# STM32.net
KiCad netlist of a schematic drawn in Altium Designer
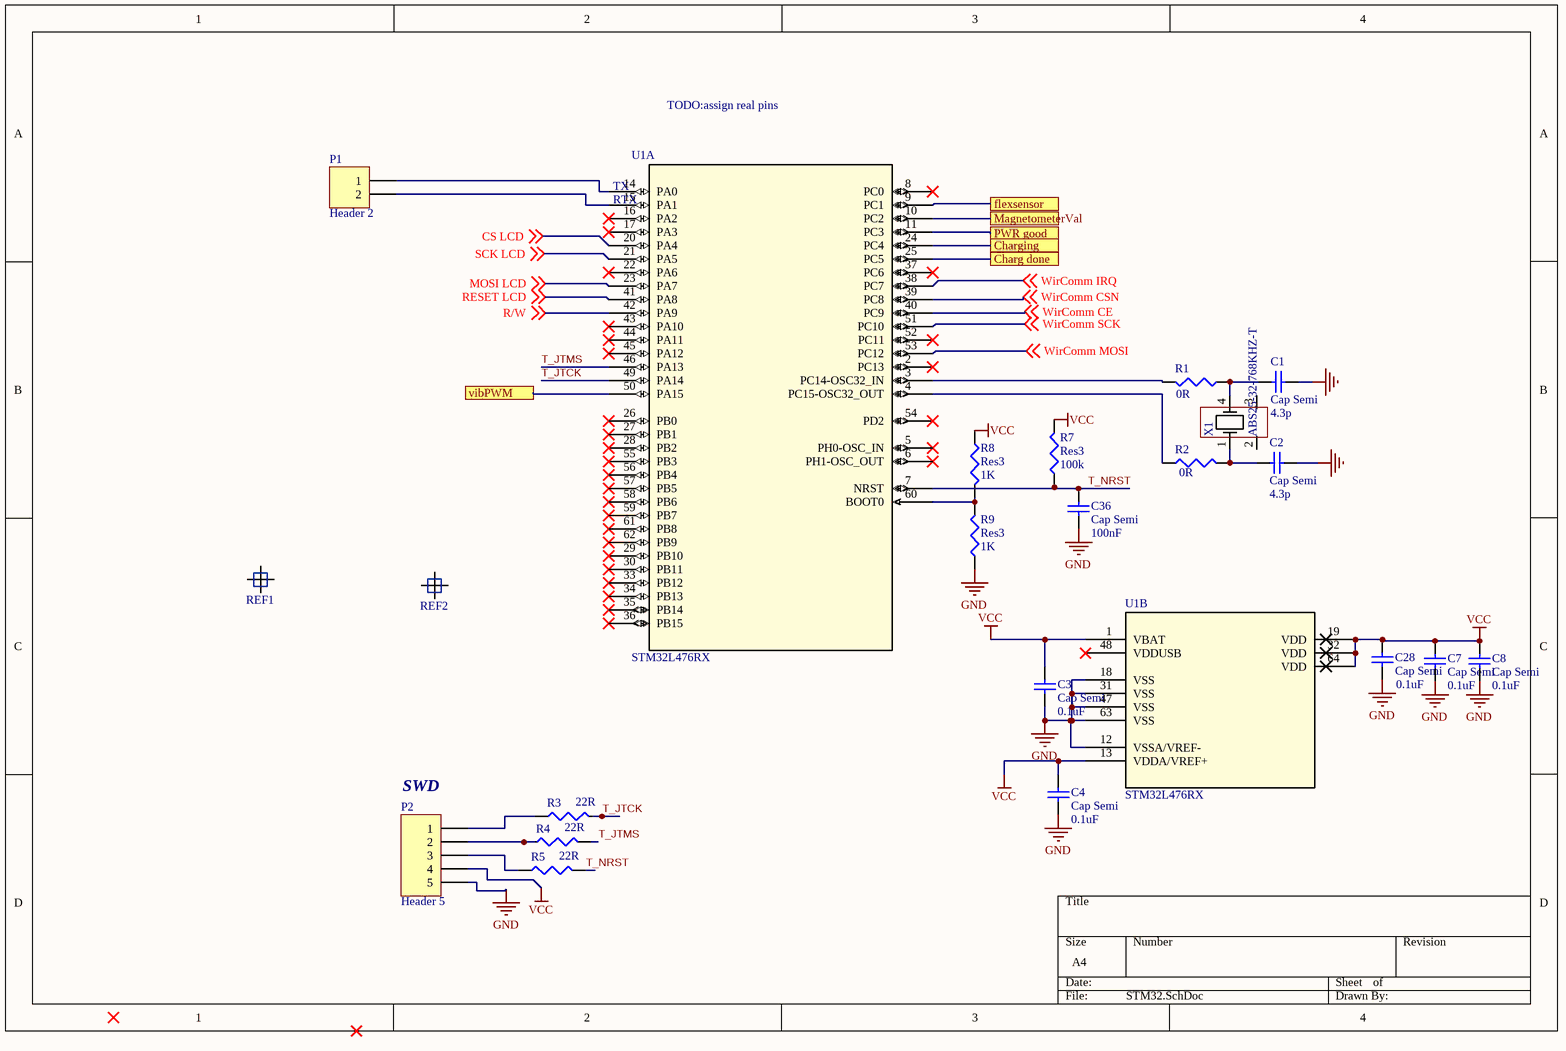
[diagram p0: STM32.SchDoc]

(export (version "E")
  (design (tool "Eeschema 10.0.6"))
  (components
    (comp (ref "C1")
      (value "Cap Semi")
      (footprint "1608[0603]")
      (description "Capacitor (Semiconductor SIM Model)")
      (fields (field (name "ALTIUM_VALUE") "4.3p") (field (name "PUBLISHER") "Altium Limited"))
      (libsource (lib "Miscellaneous Devices") (part "Cap Semi"))
    )
    (comp (ref "C2")
      (value "Cap Semi")
      (footprint "1608[0603]")
      (description "Capacitor (Semiconductor SIM Model)")
      (fields (field (name "ALTIUM_VALUE") "4.3p") (field (name "PUBLISHER") "Altium Limited"))
      (libsource (lib "Miscellaneous Devices") (part "Cap Semi"))
    )
    (comp (ref "C3")
      (value "Cap Semi")
      (footprint "1608[0603]")
      (description "Capacitor (Semiconductor SIM Model)")
      (fields (field (name "ALTIUM_VALUE") "0.1uF") (field (name "PUBLISHER") "Altium Limited"))
      (libsource (lib "Miscellaneous Devices") (part "Cap Semi"))
    )
    (comp (ref "C4")
      (value "Cap Semi")
      (footprint "1608[0603]")
      (description "Capacitor (Semiconductor SIM Model)")
      (fields (field (name "ALTIUM_VALUE") "0.1uF") (field (name "PUBLISHER") "Altium Limited"))
      (libsource (lib "Miscellaneous Devices") (part "Cap Semi"))
    )
    (comp (ref "C7")
      (value "Cap Semi")
      (footprint "1608[0603]")
      (description "Capacitor (Semiconductor SIM Model)")
      (fields (field (name "ALTIUM_VALUE") "0.1uF") (field (name "PUBLISHER") "Altium Limited"))
      (libsource (lib "Miscellaneous Devices") (part "Cap Semi"))
    )
    (comp (ref "C8")
      (value "Cap Semi")
      (footprint "1608[0603]")
      (description "Capacitor (Semiconductor SIM Model)")
      (fields (field (name "ALTIUM_VALUE") "0.1uF") (field (name "PUBLISHER") "Altium Limited"))
      (libsource (lib "Miscellaneous Devices") (part "Cap Semi"))
    )
    (comp (ref "C28")
      (value "Cap Semi")
      (footprint "1608[0603]")
      (description "Capacitor (Semiconductor SIM Model)")
      (fields (field (name "ALTIUM_VALUE") "0.1uF") (field (name "PUBLISHER") "Altium Limited"))
      (libsource (lib "Miscellaneous Devices") (part "Cap Semi"))
    )
    (comp (ref "C36")
      (value "Cap Semi")
      (footprint "1608[0603]")
      (description "Capacitor (Semiconductor SIM Model)")
      (fields (field (name "ALTIUM_VALUE") "100nF") (field (name "PUBLISHER") "Altium Limited"))
      (libsource (lib "Miscellaneous Devices") (part "Cap Semi"))
    )
    (comp (ref "P1")
      (value "Header 2")
      (footprint "HDR1X2")
      (description "Header, 2-Pin")
      (fields (field (name "PUBLISHER") "Altium Limited"))
      (libsource (lib "Miscellaneous Connectors") (part "Header 2"))
    )
    (comp (ref "P2")
      (value "Header 5")
      (footprint "HDR1X5")
      (description "Header, 5-Pin")
      (fields (field (name "PUBLISHER") "Altium Limited"))
      (libsource (lib "Miscellaneous Connectors") (part "Header 5"))
    )
    (comp (ref "R1")
      (value "0R")
      (footprint "J1-0603")
      (description "Resistor")
      (fields (field (name "Comment") "Res3") (field (name "PUBLISHER") "Altium Limited"))
      (libsource (lib "Miscellaneous Devices") (part "Res3"))
    )
    (comp (ref "R2")
      (value "0R")
      (footprint "J1-0603")
      (description "Resistor")
      (fields (field (name "Comment") "Res3") (field (name "PUBLISHER") "Altium Limited"))
      (libsource (lib "Miscellaneous Devices") (part "Res3"))
    )
    (comp (ref "R3")
      (value "22R")
      (footprint "J1-0603")
      (description "Resistor")
      (fields (field (name "PUBLISHER") "Altium Limited"))
      (libsource (lib "Miscellaneous Devices") (part "Res3"))
    )
    (comp (ref "R4")
      (value "22R")
      (footprint "J1-0603")
      (description "Resistor")
      (fields (field (name "PUBLISHER") "Altium Limited"))
      (libsource (lib "Miscellaneous Devices") (part "Res3"))
    )
    (comp (ref "R5")
      (value "22R")
      (footprint "J1-0603")
      (description "Resistor")
      (fields (field (name "PUBLISHER") "Altium Limited"))
      (libsource (lib "Miscellaneous Devices") (part "Res3"))
    )
    (comp (ref "R7")
      (value "Res3")
      (footprint "J1-0603")
      (description "Resistor")
      (fields (field (name "ALTIUM_VALUE") "100k") (field (name "PUBLISHER") "Altium Limited"))
      (libsource (lib "Miscellaneous Devices") (part "Res3"))
    )
    (comp (ref "R8")
      (value "Res3")
      (footprint "J1-0603")
      (description "Resistor")
      (fields (field (name "ALTIUM_VALUE") "1K") (field (name "PUBLISHER") "Altium Limited"))
      (libsource (lib "Miscellaneous Devices") (part "Res3"))
    )
    (comp (ref "R9")
      (value "Res3")
      (footprint "J1-0603")
      (description "Resistor")
      (fields (field (name "ALTIUM_VALUE") "1K") (field (name "PUBLISHER") "Altium Limited"))
      (libsource (lib "Miscellaneous Devices") (part "Res3"))
    )
    (comp (ref "REF1")
      (value "Fudical sq.")
      (footprint "FIDUCIAL_SQ1mm_SQ5")
      (description "Fiducal square 1mm")
      (libsource (lib "HGCDLibrary2") (part "Fudicalsquare"))
    )
    (comp (ref "REF2")
      (value "Fudical sq.")
      (footprint "FIDUCIAL_SQ1mm_SQ5")
      (description "Fiducal square 1mm")
      (libsource (lib "ScaleSCHlib1") (part "Fudicalsquare"))
    )
    (comp (ref "U1")
      (value "STM32L476RX")
      (footprint "LQFP64-10x10mm")
      (description "Imported")
      (fields
        (field (name "MANUFACTURER_PART_NUMBER") "stm32l476rx")
        (field (name "COPYRIGHT") "Copyright (C) 2016 Accelerated Designs. All rights reserved")
      )
      (libsource (lib "MainBoard") (part "STM32L476RX"))
    )
    (comp (ref "X1")
      (value "ABS25-32-768KHZ-T")
      (footprint "XTAL_ABS25-32-768KHZ-T")
      (fields (field (name "MF") "Abracon"))
      (libsource (lib "HGCDLibrary") (part "ABS25-32-768KHZ-T"))
    )
  )
  (nets
    (net (code "1") (name "/Charg done") (class "Default")
      (node (ref "U1") (pin "25") (pinfunction "PC5_25") (pintype "bidirectional"))
    )
    (net (code "2") (name "/Charging") (class "Default")
      (node (ref "U1") (pin "24") (pinfunction "PC4_24") (pintype "bidirectional"))
    )
    (net (code "3") (name "/MagnetometerVal") (class "Default")
      (node (ref "U1") (pin "10") (pinfunction "PC2_10") (pintype "bidirectional"))
    )
    (net (code "4") (name "/PWR good") (class "Default")
      (node (ref "U1") (pin "11") (pinfunction "PC3_11") (pintype "bidirectional"))
    )
    (net (code "5") (name "/T_JTCK") (class "Default")
      (node (ref "R3") (pin "2") (pinfunction "2_2") (pintype "passive"))
      (node (ref "U1") (pin "49") (pinfunction "PA14_49") (pintype "bidirectional"))
    )
    (net (code "6") (name "/T_JTMS") (class "Default")
      (node (ref "R4") (pin "2") (pinfunction "2_2") (pintype "passive"))
      (node (ref "U1") (pin "46") (pinfunction "PA13_46") (pintype "bidirectional"))
    )
    (net (code "7") (name "/T_NRST") (class "Default")
      (node (ref "C36") (pin "2") (pinfunction "2_2") (pintype "passive"))
      (node (ref "R5") (pin "2") (pinfunction "2_2") (pintype "passive"))
      (node (ref "R7") (pin "1") (pinfunction "1_1") (pintype "passive"))
      (node (ref "U1") (pin "7") (pinfunction "NRST_7") (pintype "bidirectional"))
    )
    (net (code "8") (name "/flexsensor") (class "Default")
      (node (ref "U1") (pin "9") (pinfunction "PC1_9") (pintype "bidirectional"))
    )
    (net (code "9") (name "/vibPWM") (class "Default")
      (node (ref "U1") (pin "50") (pinfunction "PA15_50") (pintype "bidirectional"))
    )
    (net (code "10") (name "CS LCD") (class "Default")
      (node (ref "U1") (pin "20") (pinfunction "PA4_20") (pintype "bidirectional"))
    )
    (net (code "11") (name "GND") (class "Default")
      (node (ref "C1") (pin "1") (pinfunction "1_1") (pintype "passive"))
      (node (ref "C2") (pin "1") (pinfunction "1_1") (pintype "passive"))
      (node (ref "C28") (pin "1") (pinfunction "1_1") (pintype "passive"))
      (node (ref "C3") (pin "1") (pinfunction "1_1") (pintype "passive"))
      (node (ref "C36") (pin "1") (pinfunction "1_1") (pintype "passive"))
      (node (ref "C4") (pin "1") (pinfunction "1_1") (pintype "passive"))
      (node (ref "C7") (pin "1") (pinfunction "1_1") (pintype "passive"))
      (node (ref "C8") (pin "1") (pinfunction "1_1") (pintype "passive"))
      (node (ref "P2") (pin "5") (pinfunction "5_5") (pintype "passive"))
      (node (ref "R9") (pin "1") (pinfunction "1_1") (pintype "passive"))
      (node (ref "U1") (pin "12") (pinfunction "VSSA/VREF-_12") (pintype "power_in"))
      (node (ref "U1") (pin "18") (pinfunction "VSS_18") (pintype "power_in"))
      (node (ref "U1") (pin "31") (pinfunction "VSS_31") (pintype "power_in"))
      (node (ref "U1") (pin "47") (pinfunction "VSS_47") (pintype "power_in"))
      (node (ref "U1") (pin "63") (pinfunction "VSS_63") (pintype "power_in"))
    )
    (net (code "12") (name "MOSI LCD") (class "Default")
      (node (ref "U1") (pin "23") (pinfunction "PA7_23") (pintype "bidirectional"))
    )
    (net (code "13") (name "Net-(C1-Pad2)") (class "Default")
      (node (ref "C1") (pin "2") (pinfunction "2_2") (pintype "passive"))
      (node (ref "R1") (pin "2") (pinfunction "2_2") (pintype "passive"))
      (node (ref "X1") (pin "4") (pinfunction "4_4") (pintype "passive"))
    )
    (net (code "14") (name "Net-(C2-Pad2)") (class "Default")
      (node (ref "C2") (pin "2") (pinfunction "2_2") (pintype "passive"))
      (node (ref "R2") (pin "2") (pinfunction "2_2") (pintype "passive"))
      (node (ref "X1") (pin "1") (pinfunction "1_1") (pintype "passive"))
    )
    (net (code "15") (name "Net-(P2-Pad1)") (class "Default")
      (node (ref "P2") (pin "1") (pinfunction "1_1") (pintype "passive"))
      (node (ref "R3") (pin "1") (pinfunction "1_1") (pintype "passive"))
    )
    (net (code "16") (name "Net-(P2-Pad2)") (class "Default")
      (node (ref "P2") (pin "2") (pinfunction "2_2") (pintype "passive"))
      (node (ref "R4") (pin "1") (pinfunction "1_1") (pintype "passive"))
    )
    (net (code "17") (name "Net-(P2-Pad3)") (class "Default")
      (node (ref "P2") (pin "3") (pinfunction "3_3") (pintype "passive"))
      (node (ref "R5") (pin "1") (pinfunction "1_1") (pintype "passive"))
    )
    (net (code "18") (name "Net-(U1A-BOOT0)") (class "Default")
      (node (ref "R8") (pin "2") (pinfunction "2_2") (pintype "passive"))
      (node (ref "R9") (pin "2") (pinfunction "2_2") (pintype "passive"))
      (node (ref "U1") (pin "60") (pinfunction "BOOT0_60") (pintype "input"))
    )
    (net (code "19") (name "Net-(U1A-PA0)") (class "Default")
      (node (ref "P1") (pin "1") (pinfunction "1_1") (pintype "passive"))
      (node (ref "U1") (pin "14") (pinfunction "PA0_14") (pintype "bidirectional"))
    )
    (net (code "20") (name "Net-(U1A-PA1)") (class "Default")
      (node (ref "P1") (pin "2") (pinfunction "2_2") (pintype "passive"))
      (node (ref "U1") (pin "15") (pinfunction "PA1_15") (pintype "bidirectional"))
    )
    (net (code "21") (name "Net-(U1A-PC14-OSC32_IN)") (class "Default")
      (node (ref "R1") (pin "1") (pinfunction "1_1") (pintype "passive"))
      (node (ref "U1") (pin "3") (pinfunction "PC14-OSC32_IN_3") (pintype "bidirectional"))
    )
    (net (code "22") (name "Net-(U1A-PC15-OSC32_OUT)") (class "Default")
      (node (ref "R2") (pin "1") (pinfunction "1_1") (pintype "passive"))
      (node (ref "U1") (pin "4") (pinfunction "PC15-OSC32_OUT_4") (pintype "bidirectional"))
    )
    (net (code "23") (name "RESET LCD") (class "Default")
      (node (ref "U1") (pin "41") (pinfunction "PA8_41") (pintype "bidirectional"))
    )
    (net (code "24") (name "R{slash}W") (class "Default")
      (node (ref "U1") (pin "42") (pinfunction "PA9_42") (pintype "bidirectional"))
    )
    (net (code "25") (name "SCK LCD") (class "Default")
      (node (ref "U1") (pin "21") (pinfunction "PA5_21") (pintype "bidirectional"))
    )
    (net (code "26") (name "VCC") (class "Default")
      (node (ref "C28") (pin "2") (pinfunction "2_2") (pintype "passive"))
      (node (ref "C3") (pin "2") (pinfunction "2_2") (pintype "passive"))
      (node (ref "C4") (pin "2") (pinfunction "2_2") (pintype "passive"))
      (node (ref "C7") (pin "2") (pinfunction "2_2") (pintype "passive"))
      (node (ref "C8") (pin "2") (pinfunction "2_2") (pintype "passive"))
      (node (ref "P2") (pin "4") (pinfunction "4_4") (pintype "passive"))
      (node (ref "R7") (pin "2") (pinfunction "2_2") (pintype "passive"))
      (node (ref "R8") (pin "1") (pinfunction "1_1") (pintype "passive"))
      (node (ref "U1") (pin "1") (pinfunction "VBAT_1") (pintype "power_in"))
      (node (ref "U1") (pin "13") (pinfunction "VDDA/VREF+_13") (pintype "power_in"))
      (node (ref "U1") (pin "19") (pinfunction "VDD_19") (pintype "power_in"))
      (node (ref "U1") (pin "32") (pinfunction "VDD_32") (pintype "power_in"))
      (node (ref "U1") (pin "64") (pinfunction "VDD_64") (pintype "power_in"))
    )
    (net (code "27") (name "WirComm CE") (class "Default")
      (node (ref "U1") (pin "40") (pinfunction "PC9_40") (pintype "bidirectional"))
    )
    (net (code "28") (name "WirComm CSN") (class "Default")
      (node (ref "U1") (pin "39") (pinfunction "PC8_39") (pintype "bidirectional"))
    )
    (net (code "29") (name "WirComm IRQ") (class "Default")
      (node (ref "U1") (pin "38") (pinfunction "PC7_38") (pintype "bidirectional"))
    )
    (net (code "30") (name "WirComm MOSI") (class "Default")
      (node (ref "U1") (pin "53") (pinfunction "PC12_53") (pintype "bidirectional"))
    )
    (net (code "31") (name "WirComm SCK") (class "Default")
      (node (ref "U1") (pin "51") (pinfunction "PC10_51") (pintype "bidirectional"))
    )
    (net (code "32") (name "unconnected-(U1A-PA2-Pad16)") (class "Default")
      (node (ref "U1") (pin "16") (pinfunction "PA2_16") (pintype "bidirectional+no_connect"))
    )
    (net (code "33") (name "unconnected-(U1A-PA3-Pad17)") (class "Default")
      (node (ref "U1") (pin "17") (pinfunction "PA3_17") (pintype "bidirectional+no_connect"))
    )
    (net (code "34") (name "unconnected-(U1A-PA6-Pad22)") (class "Default")
      (node (ref "U1") (pin "22") (pinfunction "PA6_22") (pintype "bidirectional+no_connect"))
    )
    (net (code "35") (name "unconnected-(U1A-PA10-Pad43)") (class "Default")
      (node (ref "U1") (pin "43") (pinfunction "PA10_43") (pintype "bidirectional+no_connect"))
    )
    (net (code "36") (name "unconnected-(U1A-PA11-Pad44)") (class "Default")
      (node (ref "U1") (pin "44") (pinfunction "PA11_44") (pintype "bidirectional+no_connect"))
    )
    (net (code "37") (name "unconnected-(U1A-PA12-Pad45)") (class "Default")
      (node (ref "U1") (pin "45") (pinfunction "PA12_45") (pintype "bidirectional+no_connect"))
    )
    (net (code "38") (name "unconnected-(U1A-PB0-Pad26)") (class "Default")
      (node (ref "U1") (pin "26") (pinfunction "PB0_26") (pintype "bidirectional+no_connect"))
    )
    (net (code "39") (name "unconnected-(U1A-PB1-Pad27)") (class "Default")
      (node (ref "U1") (pin "27") (pinfunction "PB1_27") (pintype "bidirectional+no_connect"))
    )
    (net (code "40") (name "unconnected-(U1A-PB2-Pad28)") (class "Default")
      (node (ref "U1") (pin "28") (pinfunction "PB2_28") (pintype "bidirectional+no_connect"))
    )
    (net (code "41") (name "unconnected-(U1A-PB3-Pad55)") (class "Default")
      (node (ref "U1") (pin "55") (pinfunction "PB3_55") (pintype "bidirectional+no_connect"))
    )
    (net (code "42") (name "unconnected-(U1A-PB4-Pad56)") (class "Default")
      (node (ref "U1") (pin "56") (pinfunction "PB4_56") (pintype "bidirectional+no_connect"))
    )
    (net (code "43") (name "unconnected-(U1A-PB5-Pad57)") (class "Default")
      (node (ref "U1") (pin "57") (pinfunction "PB5_57") (pintype "bidirectional+no_connect"))
    )
    (net (code "44") (name "unconnected-(U1A-PB6-Pad58)") (class "Default")
      (node (ref "U1") (pin "58") (pinfunction "PB6_58") (pintype "bidirectional+no_connect"))
    )
    (net (code "45") (name "unconnected-(U1A-PB7-Pad59)") (class "Default")
      (node (ref "U1") (pin "59") (pinfunction "PB7_59") (pintype "bidirectional+no_connect"))
    )
    (net (code "46") (name "unconnected-(U1A-PB8-Pad61)") (class "Default")
      (node (ref "U1") (pin "61") (pinfunction "PB8_61") (pintype "bidirectional+no_connect"))
    )
    (net (code "47") (name "unconnected-(U1A-PB9-Pad62)") (class "Default")
      (node (ref "U1") (pin "62") (pinfunction "PB9_62") (pintype "bidirectional+no_connect"))
    )
    (net (code "48") (name "unconnected-(U1A-PB10-Pad29)") (class "Default")
      (node (ref "U1") (pin "29") (pinfunction "PB10_29") (pintype "bidirectional+no_connect"))
    )
    (net (code "49") (name "unconnected-(U1A-PB11-Pad30)") (class "Default")
      (node (ref "U1") (pin "30") (pinfunction "PB11_30") (pintype "bidirectional+no_connect"))
    )
    (net (code "50") (name "unconnected-(U1A-PB12-Pad33)") (class "Default")
      (node (ref "U1") (pin "33") (pinfunction "PB12_33") (pintype "bidirectional+no_connect"))
    )
    (net (code "51") (name "unconnected-(U1A-PB13-Pad34)") (class "Default")
      (node (ref "U1") (pin "34") (pinfunction "PB13_34") (pintype "bidirectional+no_connect"))
    )
    (net (code "52") (name "unconnected-(U1A-PB14-Pad35)") (class "Default")
      (node (ref "U1") (pin "35") (pinfunction "PB14_35") (pintype "bidirectional+no_connect"))
    )
    (net (code "53") (name "unconnected-(U1A-PB15-Pad36)") (class "Default")
      (node (ref "U1") (pin "36") (pinfunction "PB15_36") (pintype "bidirectional+no_connect"))
    )
    (net (code "54") (name "unconnected-(U1A-PC0-Pad8)") (class "Default")
      (node (ref "U1") (pin "8") (pinfunction "PC0_8") (pintype "bidirectional+no_connect"))
    )
    (net (code "55") (name "unconnected-(U1A-PC6-Pad37)") (class "Default")
      (node (ref "U1") (pin "37") (pinfunction "PC6_37") (pintype "bidirectional+no_connect"))
    )
    (net (code "56") (name "unconnected-(U1A-PC11-Pad52)") (class "Default")
      (node (ref "U1") (pin "52") (pinfunction "PC11_52") (pintype "bidirectional+no_connect"))
    )
    (net (code "57") (name "unconnected-(U1A-PC13-Pad2)") (class "Default")
      (node (ref "U1") (pin "2") (pinfunction "PC13_2") (pintype "bidirectional+no_connect"))
    )
    (net (code "58") (name "unconnected-(U1A-PD2-Pad54)") (class "Default")
      (node (ref "U1") (pin "54") (pinfunction "PD2_54") (pintype "bidirectional+no_connect"))
    )
    (net (code "59") (name "unconnected-(U1A-PH0-OSC_IN-Pad5)") (class "Default")
      (node (ref "U1") (pin "5") (pinfunction "PH0-OSC_IN_5") (pintype "bidirectional+no_connect"))
    )
    (net (code "60") (name "unconnected-(U1A-PH1-OSC_OUT-Pad6)") (class "Default")
      (node (ref "U1") (pin "6") (pinfunction "PH1-OSC_OUT_6") (pintype "bidirectional+no_connect"))
    )
    (net (code "61") (name "unconnected-(U1B-VDDUSB-Pad48)") (class "Default")
      (node (ref "U1") (pin "48") (pinfunction "VDDUSB_48") (pintype "power_in+no_connect"))
    )
    (net (code "62") (name "unconnected-(X1-Pad2)") (class "Default")
      (node (ref "X1") (pin "2") (pinfunction "2_2") (pintype "passive"))
    )
    (net (code "63") (name "unconnected-(X1-Pad3)") (class "Default")
      (node (ref "X1") (pin "3") (pinfunction "3_3") (pintype "passive"))
    )
  )
)
